# main.net
KiCad netlist of a schematic drawn in EAGLE
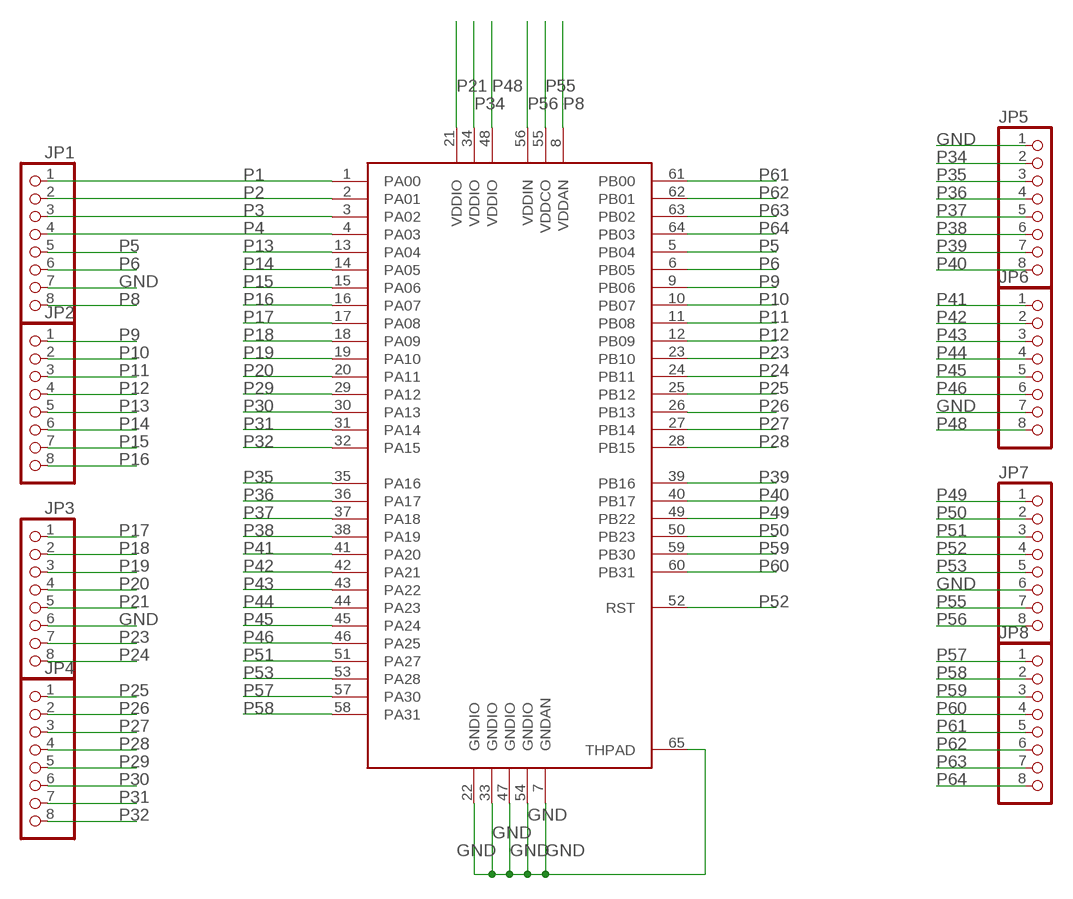
[diagram p0: schematic, sheet 1]

(export (version "E")
  (design (tool "Eeschema 10.0.6"))
  (components
    (comp (ref "JP1")
      (value "PINHD-1X8CLEANBIG")
      (footprint "eagle-import:1X08-CLEANBIG")
      (libsource (lib "eagle-import") (part "PINHD-1X8CLEANBIG"))
    )
    (comp (ref "JP2")
      (value "PINHD-1X8CLEANBIG")
      (footprint "eagle-import:1X08-CLEANBIG")
      (libsource (lib "eagle-import") (part "PINHD-1X8CLEANBIG"))
    )
    (comp (ref "JP3")
      (value "PINHD-1X8CLEANBIG")
      (footprint "eagle-import:1X08-CLEANBIG")
      (libsource (lib "eagle-import") (part "PINHD-1X8CLEANBIG"))
    )
    (comp (ref "JP4")
      (value "PINHD-1X8CLEANBIG")
      (footprint "eagle-import:1X08-CLEANBIG")
      (libsource (lib "eagle-import") (part "PINHD-1X8CLEANBIG"))
    )
    (comp (ref "JP5")
      (value "PINHD-1X8CLEANBIG")
      (footprint "eagle-import:1X08-CLEANBIG")
      (libsource (lib "eagle-import") (part "PINHD-1X8CLEANBIG"))
    )
    (comp (ref "JP6")
      (value "PINHD-1X8CLEANBIG")
      (footprint "eagle-import:1X08-CLEANBIG")
      (libsource (lib "eagle-import") (part "PINHD-1X8CLEANBIG"))
    )
    (comp (ref "JP7")
      (value "PINHD-1X8CLEANBIG")
      (footprint "eagle-import:1X08-CLEANBIG")
      (libsource (lib "eagle-import") (part "PINHD-1X8CLEANBIG"))
    )
    (comp (ref "JP8")
      (value "PINHD-1X8CLEANBIG")
      (footprint "eagle-import:1X08-CLEANBIG")
      (libsource (lib "eagle-import") (part "PINHD-1X8CLEANBIG"))
    )
    (comp (ref "U$1")
      (value "ATSAMD21J18AQFN64")
      (footprint "eagle-import:QFN50P900X900X100-65T535")
      (libsource (lib "eagle-import") (part "ATSAMD21J18AQFN64"))
    )
  )
  (nets
    (net (code "1") (name "/GND") (class "Default")
      (node (ref "JP1") (pin "7") (pinfunction "7_7") (pintype "passive"))
      (node (ref "JP3") (pin "6") (pinfunction "6_6") (pintype "passive"))
      (node (ref "JP5") (pin "1") (pinfunction "1_1") (pintype "passive"))
      (node (ref "JP6") (pin "7") (pinfunction "7_7") (pintype "passive"))
      (node (ref "JP7") (pin "6") (pinfunction "6_6") (pintype "passive"))
      (node (ref "U$1") (pin "22") (pinfunction "GNDIO_22") (pintype "bidirectional"))
      (node (ref "U$1") (pin "33") (pinfunction "GNDIO_33") (pintype "bidirectional"))
      (node (ref "U$1") (pin "47") (pinfunction "GNDIO_47") (pintype "bidirectional"))
      (node (ref "U$1") (pin "54") (pinfunction "GNDIO_54") (pintype "bidirectional"))
      (node (ref "U$1") (pin "65") (pinfunction "THPAD_65") (pintype "bidirectional"))
      (node (ref "U$1") (pin "7") (pinfunction "GNDAN_7") (pintype "bidirectional"))
    )
    (net (code "2") (name "/P1") (class "Default")
      (node (ref "JP1") (pin "1") (pinfunction "1_1") (pintype "passive"))
      (node (ref "U$1") (pin "1") (pinfunction "PA00_1") (pintype "bidirectional"))
    )
    (net (code "3") (name "/P2") (class "Default")
      (node (ref "JP1") (pin "2") (pinfunction "2_2") (pintype "passive"))
      (node (ref "U$1") (pin "2") (pinfunction "PA01_2") (pintype "bidirectional"))
    )
    (net (code "4") (name "/P3") (class "Default")
      (node (ref "JP1") (pin "3") (pinfunction "3_3") (pintype "passive"))
      (node (ref "U$1") (pin "3") (pinfunction "PA02_3") (pintype "bidirectional"))
    )
    (net (code "5") (name "/P4") (class "Default")
      (node (ref "JP1") (pin "4") (pinfunction "4_4") (pintype "passive"))
      (node (ref "U$1") (pin "4") (pinfunction "PA03_4") (pintype "bidirectional"))
    )
    (net (code "6") (name "/P5") (class "Default")
      (node (ref "JP1") (pin "5") (pinfunction "5_5") (pintype "passive"))
      (node (ref "U$1") (pin "5") (pinfunction "PB04_5") (pintype "bidirectional"))
    )
    (net (code "7") (name "/P6") (class "Default")
      (node (ref "JP1") (pin "6") (pinfunction "6_6") (pintype "passive"))
      (node (ref "U$1") (pin "6") (pinfunction "PB05_6") (pintype "bidirectional"))
    )
    (net (code "8") (name "/P8") (class "Default")
      (node (ref "JP1") (pin "8") (pinfunction "8_8") (pintype "passive"))
      (node (ref "U$1") (pin "8") (pinfunction "VDDAN_8") (pintype "bidirectional"))
    )
    (net (code "9") (name "/P9") (class "Default")
      (node (ref "JP2") (pin "1") (pinfunction "1_1") (pintype "passive"))
      (node (ref "U$1") (pin "9") (pinfunction "PB06_9") (pintype "bidirectional"))
    )
    (net (code "10") (name "/P10") (class "Default")
      (node (ref "JP2") (pin "2") (pinfunction "2_2") (pintype "passive"))
      (node (ref "U$1") (pin "10") (pinfunction "PB07_10") (pintype "bidirectional"))
    )
    (net (code "11") (name "/P11") (class "Default")
      (node (ref "JP2") (pin "3") (pinfunction "3_3") (pintype "passive"))
      (node (ref "U$1") (pin "11") (pinfunction "PB08_11") (pintype "bidirectional"))
    )
    (net (code "12") (name "/P12") (class "Default")
      (node (ref "JP2") (pin "4") (pinfunction "4_4") (pintype "passive"))
      (node (ref "U$1") (pin "12") (pinfunction "PB09_12") (pintype "bidirectional"))
    )
    (net (code "13") (name "/P13") (class "Default")
      (node (ref "JP2") (pin "5") (pinfunction "5_5") (pintype "passive"))
      (node (ref "U$1") (pin "13") (pinfunction "PA04_13") (pintype "bidirectional"))
    )
    (net (code "14") (name "/P14") (class "Default")
      (node (ref "JP2") (pin "6") (pinfunction "6_6") (pintype "passive"))
      (node (ref "U$1") (pin "14") (pinfunction "PA05_14") (pintype "bidirectional"))
    )
    (net (code "15") (name "/P15") (class "Default")
      (node (ref "JP2") (pin "7") (pinfunction "7_7") (pintype "passive"))
      (node (ref "U$1") (pin "15") (pinfunction "PA06_15") (pintype "bidirectional"))
    )
    (net (code "16") (name "/P16") (class "Default")
      (node (ref "JP2") (pin "8") (pinfunction "8_8") (pintype "passive"))
      (node (ref "U$1") (pin "16") (pinfunction "PA07_16") (pintype "bidirectional"))
    )
    (net (code "17") (name "/P17") (class "Default")
      (node (ref "JP3") (pin "1") (pinfunction "1_1") (pintype "passive"))
      (node (ref "U$1") (pin "17") (pinfunction "PA08_17") (pintype "bidirectional"))
    )
    (net (code "18") (name "/P18") (class "Default")
      (node (ref "JP3") (pin "2") (pinfunction "2_2") (pintype "passive"))
      (node (ref "U$1") (pin "18") (pinfunction "PA09_18") (pintype "bidirectional"))
    )
    (net (code "19") (name "/P19") (class "Default")
      (node (ref "JP3") (pin "3") (pinfunction "3_3") (pintype "passive"))
      (node (ref "U$1") (pin "19") (pinfunction "PA10_19") (pintype "bidirectional"))
    )
    (net (code "20") (name "/P20") (class "Default")
      (node (ref "JP3") (pin "4") (pinfunction "4_4") (pintype "passive"))
      (node (ref "U$1") (pin "20") (pinfunction "PA11_20") (pintype "bidirectional"))
    )
    (net (code "21") (name "/P21") (class "Default")
      (node (ref "JP3") (pin "5") (pinfunction "5_5") (pintype "passive"))
      (node (ref "U$1") (pin "21") (pinfunction "VDDIO_21") (pintype "bidirectional"))
    )
    (net (code "22") (name "/P23") (class "Default")
      (node (ref "JP3") (pin "7") (pinfunction "7_7") (pintype "passive"))
      (node (ref "U$1") (pin "23") (pinfunction "PB10_23") (pintype "bidirectional"))
    )
    (net (code "23") (name "/P24") (class "Default")
      (node (ref "JP3") (pin "8") (pinfunction "8_8") (pintype "passive"))
      (node (ref "U$1") (pin "24") (pinfunction "PB11_24") (pintype "bidirectional"))
    )
    (net (code "24") (name "/P25") (class "Default")
      (node (ref "JP4") (pin "1") (pinfunction "1_1") (pintype "passive"))
      (node (ref "U$1") (pin "25") (pinfunction "PB12_25") (pintype "bidirectional"))
    )
    (net (code "25") (name "/P26") (class "Default")
      (node (ref "JP4") (pin "2") (pinfunction "2_2") (pintype "passive"))
      (node (ref "U$1") (pin "26") (pinfunction "PB13_26") (pintype "bidirectional"))
    )
    (net (code "26") (name "/P27") (class "Default")
      (node (ref "JP4") (pin "3") (pinfunction "3_3") (pintype "passive"))
      (node (ref "U$1") (pin "27") (pinfunction "PB14_27") (pintype "bidirectional"))
    )
    (net (code "27") (name "/P28") (class "Default")
      (node (ref "JP4") (pin "4") (pinfunction "4_4") (pintype "passive"))
      (node (ref "U$1") (pin "28") (pinfunction "PB15_28") (pintype "bidirectional"))
    )
    (net (code "28") (name "/P29") (class "Default")
      (node (ref "JP4") (pin "5") (pinfunction "5_5") (pintype "passive"))
      (node (ref "U$1") (pin "29") (pinfunction "PA12_29") (pintype "bidirectional"))
    )
    (net (code "29") (name "/P30") (class "Default")
      (node (ref "JP4") (pin "6") (pinfunction "6_6") (pintype "passive"))
      (node (ref "U$1") (pin "30") (pinfunction "PA13_30") (pintype "bidirectional"))
    )
    (net (code "30") (name "/P31") (class "Default")
      (node (ref "JP4") (pin "7") (pinfunction "7_7") (pintype "passive"))
      (node (ref "U$1") (pin "31") (pinfunction "PA14_31") (pintype "bidirectional"))
    )
    (net (code "31") (name "/P32") (class "Default")
      (node (ref "JP4") (pin "8") (pinfunction "8_8") (pintype "passive"))
      (node (ref "U$1") (pin "32") (pinfunction "PA15_32") (pintype "bidirectional"))
    )
    (net (code "32") (name "/P34") (class "Default")
      (node (ref "JP5") (pin "2") (pinfunction "2_2") (pintype "passive"))
      (node (ref "U$1") (pin "34") (pinfunction "VDDIO_34") (pintype "bidirectional"))
    )
    (net (code "33") (name "/P35") (class "Default")
      (node (ref "JP5") (pin "3") (pinfunction "3_3") (pintype "passive"))
      (node (ref "U$1") (pin "35") (pinfunction "PA16_35") (pintype "bidirectional"))
    )
    (net (code "34") (name "/P36") (class "Default")
      (node (ref "JP5") (pin "4") (pinfunction "4_4") (pintype "passive"))
      (node (ref "U$1") (pin "36") (pinfunction "PA17_36") (pintype "bidirectional"))
    )
    (net (code "35") (name "/P37") (class "Default")
      (node (ref "JP5") (pin "5") (pinfunction "5_5") (pintype "passive"))
      (node (ref "U$1") (pin "37") (pinfunction "PA18_37") (pintype "bidirectional"))
    )
    (net (code "36") (name "/P38") (class "Default")
      (node (ref "JP5") (pin "6") (pinfunction "6_6") (pintype "passive"))
      (node (ref "U$1") (pin "38") (pinfunction "PA19_38") (pintype "bidirectional"))
    )
    (net (code "37") (name "/P39") (class "Default")
      (node (ref "JP5") (pin "7") (pinfunction "7_7") (pintype "passive"))
      (node (ref "U$1") (pin "39") (pinfunction "PB16_39") (pintype "bidirectional"))
    )
    (net (code "38") (name "/P40") (class "Default")
      (node (ref "JP5") (pin "8") (pinfunction "8_8") (pintype "passive"))
      (node (ref "U$1") (pin "40") (pinfunction "PB17_40") (pintype "bidirectional"))
    )
    (net (code "39") (name "/P41") (class "Default")
      (node (ref "JP6") (pin "1") (pinfunction "1_1") (pintype "passive"))
      (node (ref "U$1") (pin "41") (pinfunction "PA20_41") (pintype "bidirectional"))
    )
    (net (code "40") (name "/P42") (class "Default")
      (node (ref "JP6") (pin "2") (pinfunction "2_2") (pintype "passive"))
      (node (ref "U$1") (pin "42") (pinfunction "PA21_42") (pintype "bidirectional"))
    )
    (net (code "41") (name "/P43") (class "Default")
      (node (ref "JP6") (pin "3") (pinfunction "3_3") (pintype "passive"))
      (node (ref "U$1") (pin "43") (pinfunction "PA22_43") (pintype "bidirectional"))
    )
    (net (code "42") (name "/P44") (class "Default")
      (node (ref "JP6") (pin "4") (pinfunction "4_4") (pintype "passive"))
      (node (ref "U$1") (pin "44") (pinfunction "PA23_44") (pintype "bidirectional"))
    )
    (net (code "43") (name "/P45") (class "Default")
      (node (ref "JP6") (pin "5") (pinfunction "5_5") (pintype "passive"))
      (node (ref "U$1") (pin "45") (pinfunction "PA24_45") (pintype "bidirectional"))
    )
    (net (code "44") (name "/P46") (class "Default")
      (node (ref "JP6") (pin "6") (pinfunction "6_6") (pintype "passive"))
      (node (ref "U$1") (pin "46") (pinfunction "PA25_46") (pintype "bidirectional"))
    )
    (net (code "45") (name "/P48") (class "Default")
      (node (ref "JP6") (pin "8") (pinfunction "8_8") (pintype "passive"))
      (node (ref "U$1") (pin "48") (pinfunction "VDDIO_48") (pintype "bidirectional"))
    )
    (net (code "46") (name "/P49") (class "Default")
      (node (ref "JP7") (pin "1") (pinfunction "1_1") (pintype "passive"))
      (node (ref "U$1") (pin "49") (pinfunction "PB22_49") (pintype "bidirectional"))
    )
    (net (code "47") (name "/P50") (class "Default")
      (node (ref "JP7") (pin "2") (pinfunction "2_2") (pintype "passive"))
      (node (ref "U$1") (pin "50") (pinfunction "PB23_50") (pintype "bidirectional"))
    )
    (net (code "48") (name "/P51") (class "Default")
      (node (ref "JP7") (pin "3") (pinfunction "3_3") (pintype "passive"))
      (node (ref "U$1") (pin "51") (pinfunction "PA27_51") (pintype "bidirectional"))
    )
    (net (code "49") (name "/P52") (class "Default")
      (node (ref "JP7") (pin "4") (pinfunction "4_4") (pintype "passive"))
      (node (ref "U$1") (pin "52") (pinfunction "RST_52") (pintype "bidirectional"))
    )
    (net (code "50") (name "/P53") (class "Default")
      (node (ref "JP7") (pin "5") (pinfunction "5_5") (pintype "passive"))
      (node (ref "U$1") (pin "53") (pinfunction "PA28_53") (pintype "bidirectional"))
    )
    (net (code "51") (name "/P55") (class "Default")
      (node (ref "JP7") (pin "7") (pinfunction "7_7") (pintype "passive"))
      (node (ref "U$1") (pin "55") (pinfunction "VDDCO_55") (pintype "bidirectional"))
    )
    (net (code "52") (name "/P56") (class "Default")
      (node (ref "JP7") (pin "8") (pinfunction "8_8") (pintype "passive"))
      (node (ref "U$1") (pin "56") (pinfunction "VDDIN_56") (pintype "bidirectional"))
    )
    (net (code "53") (name "/P57") (class "Default")
      (node (ref "JP8") (pin "1") (pinfunction "1_1") (pintype "passive"))
      (node (ref "U$1") (pin "57") (pinfunction "PA30_57") (pintype "bidirectional"))
    )
    (net (code "54") (name "/P58") (class "Default")
      (node (ref "JP8") (pin "2") (pinfunction "2_2") (pintype "passive"))
      (node (ref "U$1") (pin "58") (pinfunction "PA31_58") (pintype "bidirectional"))
    )
    (net (code "55") (name "/P59") (class "Default")
      (node (ref "JP8") (pin "3") (pinfunction "3_3") (pintype "passive"))
      (node (ref "U$1") (pin "59") (pinfunction "PB30_59") (pintype "bidirectional"))
    )
    (net (code "56") (name "/P60") (class "Default")
      (node (ref "JP8") (pin "4") (pinfunction "4_4") (pintype "passive"))
      (node (ref "U$1") (pin "60") (pinfunction "PB31_60") (pintype "bidirectional"))
    )
    (net (code "57") (name "/P61") (class "Default")
      (node (ref "JP8") (pin "5") (pinfunction "5_5") (pintype "passive"))
      (node (ref "U$1") (pin "61") (pinfunction "PB00_61") (pintype "bidirectional"))
    )
    (net (code "58") (name "/P62") (class "Default")
      (node (ref "JP8") (pin "6") (pinfunction "6_6") (pintype "passive"))
      (node (ref "U$1") (pin "62") (pinfunction "PB01_62") (pintype "bidirectional"))
    )
    (net (code "59") (name "/P63") (class "Default")
      (node (ref "JP8") (pin "7") (pinfunction "7_7") (pintype "passive"))
      (node (ref "U$1") (pin "63") (pinfunction "PB02_63") (pintype "bidirectional"))
    )
    (net (code "60") (name "/P64") (class "Default")
      (node (ref "JP8") (pin "8") (pinfunction "8_8") (pintype "passive"))
      (node (ref "U$1") (pin "64") (pinfunction "PB03_64") (pintype "bidirectional"))
    )
  )
)
